# ClockBooster.net
KiCad netlist of a schematic drawn in Altium Designer
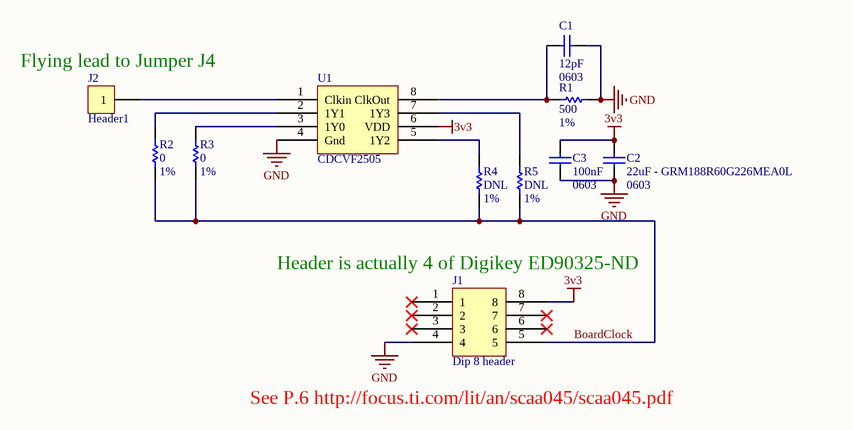
[diagram p0: ClockBooster.SchDoc]

(export (version "E")
  (design (tool "Eeschema 10.0.6"))
  (components
    (comp (ref "C1")
      (value "12pF")
      (footprint "0603")
      (description "Capacitor, Ceramic, 0603")
      (libsource (lib "AdamsParts") (part "Cap0603"))
    )
    (comp (ref "C2")
      (value "22uF - GRM188R60G226MEA0L")
      (footprint "0603")
      (description "Capacitor, Ceramic, 0603")
      (libsource (lib "AdamsParts") (part "Cap0603"))
    )
    (comp (ref "C3")
      (value "100nF")
      (footprint "0603")
      (description "Capacitor, Ceramic, 0603")
      (libsource (lib "AdamsParts") (part "Cap0603"))
    )
    (comp (ref "J1")
      (value "Dip 8 header")
      (footprint "DIP8Header")
      (libsource (lib "AdamsParts") (part "DIP8Header"))
    )
    (comp (ref "J2")
      (value "Header1")
      (footprint "HDR1")
      (description "TestPoint1")
      (libsource (lib "AdamsParts") (part "Header1"))
    )
    (comp (ref "R1")
      (value "500")
      (footprint "0603")
      (description "Resistor")
      (fields (field (name "PARAM") "1%") (field (name "Comment") "Res0603"))
      (libsource (lib "AdamsParts") (part "Res0603"))
    )
    (comp (ref "R2")
      (value "0")
      (footprint "0603")
      (description "Resistor")
      (fields (field (name "PARAM") "1%") (field (name "Comment") "Res0603"))
      (libsource (lib "AdamsParts") (part "Res0603"))
    )
    (comp (ref "R3")
      (value "0")
      (footprint "0603")
      (description "Resistor")
      (fields (field (name "PARAM") "1%") (field (name "Comment") "Res0603"))
      (libsource (lib "AdamsParts") (part "Res0603"))
    )
    (comp (ref "R4")
      (value "DNL")
      (footprint "0603")
      (description "Resistor")
      (fields (field (name "PARAM") "1%") (field (name "Comment") "Res0603"))
      (libsource (lib "AdamsParts") (part "Res0603"))
    )
    (comp (ref "R5")
      (value "DNL")
      (footprint "0603")
      (description "Resistor")
      (fields (field (name "PARAM") "1%") (field (name "Comment") "Res0603"))
      (libsource (lib "AdamsParts") (part "Res0603"))
    )
    (comp (ref "U1")
      (value "CDCVF2505")
      (footprint "SO8")
      (description "PLL 24->200Mhz PLL")
      (libsource (lib "AdamsParts") (part "CDCVF2505"))
    )
  )
  (nets
    (net (code "1") (name "/BoardClock") (class "Default")
      (node (ref "J1") (pin "5") (pinfunction "5_5") (pintype "passive"))
      (node (ref "R2") (pin "1") (pinfunction "1_1") (pintype "passive"))
      (node (ref "R3") (pin "1") (pinfunction "1_1") (pintype "passive"))
      (node (ref "R4") (pin "1") (pinfunction "1_1") (pintype "passive"))
      (node (ref "R5") (pin "1") (pinfunction "1_1") (pintype "passive"))
    )
    (net (code "2") (name "3v3") (class "Default")
      (node (ref "C2") (pin "2") (pinfunction "2_2") (pintype "passive"))
      (node (ref "C3") (pin "2") (pinfunction "2_2") (pintype "passive"))
      (node (ref "J1") (pin "8") (pinfunction "8_8") (pintype "passive"))
      (node (ref "U1") (pin "6") (pinfunction "VDD_6") (pintype "passive"))
    )
    (net (code "3") (name "GND") (class "Default")
      (node (ref "C1") (pin "1") (pinfunction "1_1") (pintype "passive"))
      (node (ref "C2") (pin "1") (pinfunction "1_1") (pintype "passive"))
      (node (ref "C3") (pin "1") (pinfunction "1_1") (pintype "passive"))
      (node (ref "J1") (pin "4") (pinfunction "4_4") (pintype "passive"))
      (node (ref "R1") (pin "1") (pinfunction "1_1") (pintype "passive"))
      (node (ref "U1") (pin "4") (pinfunction "Gnd_4") (pintype "passive"))
    )
    (net (code "4") (name "Net-(U1-1Y0)") (class "Default")
      (node (ref "R3") (pin "2") (pinfunction "2_2") (pintype "passive"))
      (node (ref "U1") (pin "3") (pinfunction "1Y0_3") (pintype "passive"))
    )
    (net (code "5") (name "Net-(U1-1Y1)") (class "Default")
      (node (ref "R2") (pin "2") (pinfunction "2_2") (pintype "passive"))
      (node (ref "U1") (pin "2") (pinfunction "1Y1_2") (pintype "passive"))
    )
    (net (code "6") (name "Net-(U1-1Y2)") (class "Default")
      (node (ref "R4") (pin "2") (pinfunction "2_2") (pintype "passive"))
      (node (ref "U1") (pin "5") (pinfunction "1Y2_5") (pintype "passive"))
    )
    (net (code "7") (name "Net-(U1-1Y3)") (class "Default")
      (node (ref "R5") (pin "2") (pinfunction "2_2") (pintype "passive"))
      (node (ref "U1") (pin "7") (pinfunction "1Y3_7") (pintype "passive"))
    )
    (net (code "8") (name "Net-(U1-ClkOut)") (class "Default")
      (node (ref "C1") (pin "2") (pinfunction "2_2") (pintype "passive"))
      (node (ref "R1") (pin "2") (pinfunction "2_2") (pintype "passive"))
      (node (ref "U1") (pin "8") (pinfunction "ClkOut_8") (pintype "passive"))
    )
    (net (code "9") (name "Net-(U1-Clkin)") (class "Default")
      (node (ref "J2") (pin "1") (pinfunction "1_1") (pintype "passive"))
      (node (ref "U1") (pin "1") (pinfunction "Clkin_1") (pintype "passive"))
    )
    (net (code "10") (name "unconnected-(J1-Pad1)") (class "Default")
      (node (ref "J1") (pin "1") (pinfunction "1_1") (pintype "passive+no_connect"))
    )
    (net (code "11") (name "unconnected-(J1-Pad2)") (class "Default")
      (node (ref "J1") (pin "2") (pinfunction "2_2") (pintype "passive+no_connect"))
    )
    (net (code "12") (name "unconnected-(J1-Pad3)") (class "Default")
      (node (ref "J1") (pin "3") (pinfunction "3_3") (pintype "passive+no_connect"))
    )
    (net (code "13") (name "unconnected-(J1-Pad6)") (class "Default")
      (node (ref "J1") (pin "6") (pinfunction "6_6") (pintype "passive+no_connect"))
    )
    (net (code "14") (name "unconnected-(J1-Pad7)") (class "Default")
      (node (ref "J1") (pin "7") (pinfunction "7_7") (pintype "passive+no_connect"))
    )
  )
)
